# Sheet2.net
KiCad netlist of a schematic drawn in Altium Designer
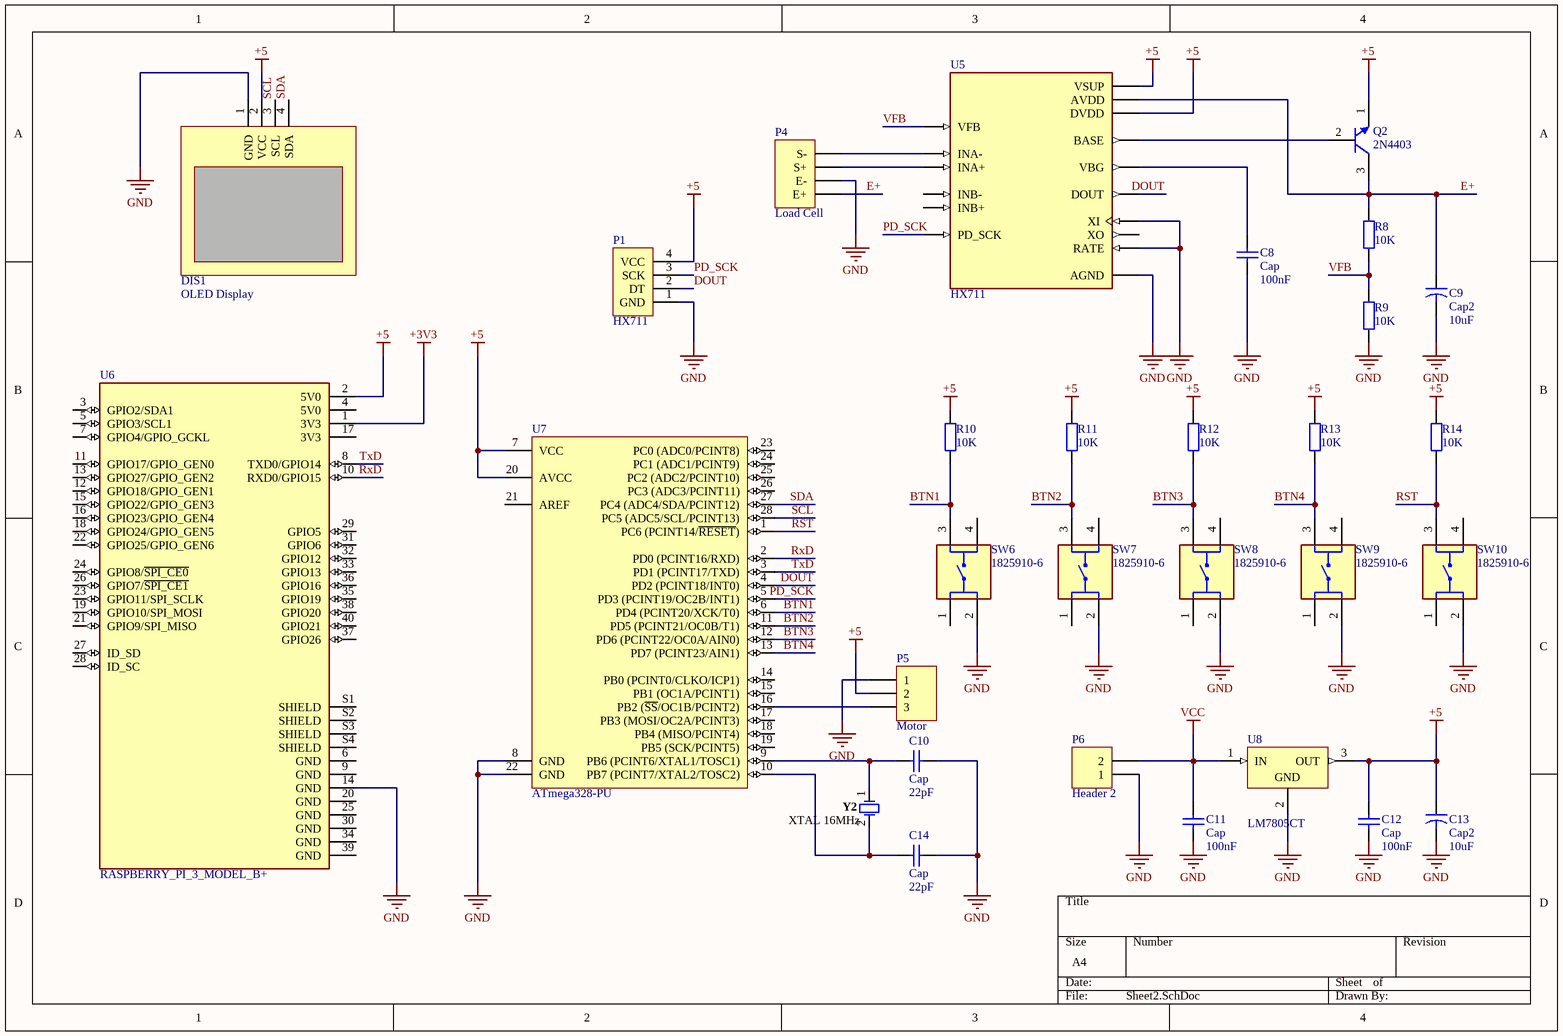
[diagram p0: Sheet2.SchDoc]

(export (version "E")
  (design (tool "Eeschema 10.0.6"))
  (components
    (comp (ref "C8")
      (value "Cap")
      (footprint "RAD-0.2")
      (description "Capacitor")
      (fields (field (name "ALTIUM_VALUE") "100nF") (field (name "PUBLISHER") "Altium Limited"))
      (libsource (lib "Miscellaneous Devices") (part "Cap"))
    )
    (comp (ref "C9")
      (value "Cap2")
      (footprint "R38")
      (description "Capacitor")
      (fields (field (name "ALTIUM_VALUE") "10uF") (field (name "PUBLISHER") "Altium Limited"))
      (libsource (lib "Miscellaneous Devices") (part "Cap2"))
    )
    (comp (ref "C10")
      (value "Cap")
      (footprint "RAD-0.1")
      (description "Capacitor")
      (fields (field (name "ALTIUM_VALUE") "22pF") (field (name "PUBLISHER") "Altium Limited"))
      (libsource (lib "Miscellaneous Devices") (part "Cap"))
    )
    (comp (ref "C11")
      (value "Cap")
      (footprint "RAD-0.2")
      (description "Capacitor")
      (fields (field (name "ALTIUM_VALUE") "100nF") (field (name "PUBLISHER") "Altium Limited"))
      (libsource (lib "Miscellaneous Devices") (part "Cap"))
    )
    (comp (ref "C12")
      (value "Cap")
      (footprint "RAD-0.2")
      (description "Capacitor")
      (fields (field (name "ALTIUM_VALUE") "100nF") (field (name "PUBLISHER") "Altium Limited"))
      (libsource (lib "Miscellaneous Devices") (part "Cap"))
    )
    (comp (ref "C13")
      (value "Cap2")
      (footprint "R38")
      (description "Capacitor")
      (fields (field (name "ALTIUM_VALUE") "10uF") (field (name "PUBLISHER") "Altium Limited"))
      (libsource (lib "Miscellaneous Devices") (part "Cap2"))
    )
    (comp (ref "C14")
      (value "Cap")
      (footprint "RAD-0.1")
      (description "Capacitor")
      (fields (field (name "ALTIUM_VALUE") "22pF") (field (name "PUBLISHER") "Altium Limited"))
      (libsource (lib "Miscellaneous Devices") (part "Cap"))
    )
    (comp (ref "DIS1")
      (value "OLED Display")
      (footprint "OLED12864I2C")
      (libsource (lib "OLED12864I2C") (part "OLED12864I2C"))
    )
    (comp (ref "P1")
      (value "HX711")
      (footprint "HDR1X4")
      (description "Header, 4-Pin")
      (fields (field (name "PUBLISHER") "Altium Limited"))
      (libsource (lib "") (part "Header 4_1"))
    )
    (comp (ref "P4")
      (value "Load Cell")
      (footprint "HDR1X4")
      (description "Load Cell Connector, 4-Pin")
      (fields (field (name "PUBLISHER") "Altium Limited"))
      (libsource (lib "Miscellaneous Connectors") (part "Header 4"))
    )
    (comp (ref "P5")
      (value "Motor")
      (footprint "HDR1X3")
      (description "Header, 3-Pin")
      (fields (field (name "PUBLISHER") "Altium Limited"))
      (libsource (lib "Miscellaneous Connectors") (part "Header 3"))
    )
    (comp (ref "P6")
      (value "Header 2")
      (footprint "HDR1X2")
      (description "Header, 2-Pin")
      (fields (field (name "PUBLISHER") "Altium Limited"))
      (libsource (lib "Miscellaneous Connectors") (part "Header 2"))
    )
    (comp (ref "Q2")
      (value "2N4403")
      (footprint "ONSC-TO-92-3-29-11_AM_BL")
      (description "General Purpose Transistor, NPN Silicon, 3-Pin TO-92, Pb-Free, Ammo Box")
      (fields (field (name "PARTNUMBER") "2N4401RLRPG") (field (name "MANUFACTURER") "On Semiconductor"))
      (libsource (lib "Altium Content Vault") (part "ONSC-NPN-E1B2C3-3"))
    )
    (comp (ref "R8")
      (value "10K")
      (footprint "AXIAL-0.4")
      (description "Resistor")
      (fields (field (name "PUBLISHER") "Altium Limited"))
      (libsource (lib "Miscellaneous Devices") (part "Res2"))
    )
    (comp (ref "R9")
      (value "10K")
      (footprint "AXIAL-0.4")
      (description "Resistor")
      (fields (field (name "PUBLISHER") "Altium Limited"))
      (libsource (lib "Miscellaneous Devices") (part "Res2"))
    )
    (comp (ref "R10")
      (value "10K")
      (footprint "AXIAL-0.4")
      (description "Resistor")
      (fields (field (name "PUBLISHER") "Altium Limited"))
      (libsource (lib "Miscellaneous Devices") (part "Res2"))
    )
    (comp (ref "R11")
      (value "10K")
      (footprint "AXIAL-0.4")
      (description "Resistor")
      (fields (field (name "PUBLISHER") "Altium Limited"))
      (libsource (lib "Miscellaneous Devices") (part "Res2"))
    )
    (comp (ref "R12")
      (value "10K")
      (footprint "AXIAL-0.4")
      (description "Resistor")
      (fields (field (name "PUBLISHER") "Altium Limited"))
      (libsource (lib "Miscellaneous Devices") (part "Res2"))
    )
    (comp (ref "R13")
      (value "10K")
      (footprint "AXIAL-0.4")
      (description "Resistor")
      (fields (field (name "PUBLISHER") "Altium Limited"))
      (libsource (lib "Miscellaneous Devices") (part "Res2"))
    )
    (comp (ref "R14")
      (value "10K")
      (footprint "AXIAL-0.4")
      (description "Resistor")
      (fields (field (name "PUBLISHER") "Altium Limited"))
      (libsource (lib "Miscellaneous Devices") (part "Res2"))
    )
    (comp (ref "SW6")
      (value "1825910-6")
      (footprint "SW_1825910-6-4")
      (description "Switch Tactile OFF (ON) SPST Round Button PC Pins 0.05A 24VDC 100000Cycles 1.57N Thru-Hole Loose")
      (libsource (lib "1825910-6") (part "1825910-6"))
    )
    (comp (ref "SW7")
      (value "1825910-6")
      (footprint "SW_1825910-6-4")
      (description "Switch Tactile OFF (ON) SPST Round Button PC Pins 0.05A 24VDC 100000Cycles 1.57N Thru-Hole Loose")
      (libsource (lib "1825910-6") (part "1825910-6"))
    )
    (comp (ref "SW8")
      (value "1825910-6")
      (footprint "SW_1825910-6-4")
      (description "Switch Tactile OFF (ON) SPST Round Button PC Pins 0.05A 24VDC 100000Cycles 1.57N Thru-Hole Loose")
      (libsource (lib "1825910-6") (part "1825910-6"))
    )
    (comp (ref "SW9")
      (value "1825910-6")
      (footprint "SW_1825910-6-4")
      (description "Switch Tactile OFF (ON) SPST Round Button PC Pins 0.05A 24VDC 100000Cycles 1.57N Thru-Hole Loose")
      (libsource (lib "1825910-6") (part "1825910-6"))
    )
    (comp (ref "SW10")
      (value "1825910-6")
      (footprint "SW_1825910-6-4")
      (description "Switch Tactile OFF (ON) SPST Round Button PC Pins 0.05A 24VDC 100000Cycles 1.57N Thru-Hole Loose")
      (libsource (lib "1825910-6") (part "1825910-6"))
    )
    (comp (ref "U5")
      (value "HX711")
      (footprint "SOP127P600X180-16N")
      (libsource (lib "HX711") (part "HX711"))
    )
    (comp (ref "U6")
      (value "RASPBERRY_PI_3_MODEL_B+")
      (footprint "MODULE_RASPBERRY_PI_3_MODEL_B+")
      (description "BCM2835 Raspberry Pi Model B+ - ARM11, VideoCore MPU Embedded Evaluation Board")
      (libsource (lib "RASPBERRY_PI_3_MODEL_B_") (part "RASPBERRY_PI_3_MODEL_B+"))
    )
    (comp (ref "U7")
      (value "ATmega328-PU")
      (footprint "28P3")
      (libsource (lib "Altium Content Vault") (part "MC-8B-ATM48-IL28"))
    )
    (comp (ref "U8")
      (value "LM7805CT")
      (footprint "FAIR-TO-220-3")
      (description "Positive Voltage Regulator, 5 V, 1 A, -40 to 125 degC, 3-Pin TO-220, RoHS, Tube")
      (fields (field (name "MANUFACTURER") "FairchildSemiconductor"))
      (libsource (lib "Altium Content Vault") (part "FAIR-LM7805CT-TO220-3"))
    )
    (comp (ref "Y2")
      (value "XTAL 16MHz")
      (footprint "FOX-FOXSLF-2_V")
      (description "Resistance Weld Thru-Hole Crystal, 12 MHz, +/-30 ppm, -20 to 70 degC, 2-Pin THD, RoHS, Bulk")
      (libsource (lib "Altium Content Vault") (part "XTAL-1-2-2"))
    )
  )
  (nets
    (net (code "1") (name "+3V3") (class "Default")
      (node (ref "U6") (pin "1") (pinfunction "3V3_1") (pintype "power_in"))
    )
    (net (code "2") (name "+5") (class "Default")
      (node (ref "C12") (pin "2") (pinfunction "2_2") (pintype "passive"))
      (node (ref "C13") (pin "1") (pinfunction "1_1") (pintype "passive"))
      (node (ref "DIS1") (pin "2") (pinfunction "VCC_2") (pintype "passive"))
      (node (ref "P1") (pin "4") (pinfunction "VCC_4") (pintype "passive"))
      (node (ref "P5") (pin "2") (pinfunction "2_2") (pintype "passive"))
      (node (ref "Q2") (pin "1") (pinfunction "E_1") (pintype "passive"))
      (node (ref "R10") (pin "2") (pinfunction "2_2") (pintype "passive"))
      (node (ref "R11") (pin "2") (pinfunction "2_2") (pintype "passive"))
      (node (ref "R12") (pin "2") (pinfunction "2_2") (pintype "passive"))
      (node (ref "R13") (pin "2") (pinfunction "2_2") (pintype "passive"))
      (node (ref "R14") (pin "2") (pinfunction "2_2") (pintype "passive"))
      (node (ref "U5") (pin "1") (pinfunction "VSUP_1") (pintype "power_in"))
      (node (ref "U5") (pin "16") (pinfunction "DVDD_16") (pintype "power_in"))
      (node (ref "U6") (pin "2") (pinfunction "5V0_2") (pintype "power_in"))
      (node (ref "U7") (pin "20") (pinfunction "AVCC_20") (pintype "power_in"))
      (node (ref "U7") (pin "7") (pinfunction "VCC_7") (pintype "power_in"))
      (node (ref "U8") (pin "3") (pinfunction "OUT_3") (pintype "output"))
    )
    (net (code "3") (name "/BTN1") (class "Default")
      (node (ref "R10") (pin "1") (pinfunction "1_1") (pintype "passive"))
      (node (ref "SW6") (pin "3") (pinfunction "3_3") (pintype "passive"))
      (node (ref "U7") (pin "6") (pinfunction "PD4_(PCINT20/XCK/T0)_6") (pintype "bidirectional"))
    )
    (net (code "4") (name "/BTN2") (class "Default")
      (node (ref "R11") (pin "1") (pinfunction "1_1") (pintype "passive"))
      (node (ref "SW7") (pin "3") (pinfunction "3_3") (pintype "passive"))
      (node (ref "U7") (pin "11") (pinfunction "PD5_(PCINT21/OC0B/T1)_11") (pintype "bidirectional"))
    )
    (net (code "5") (name "/BTN3") (class "Default")
      (node (ref "R12") (pin "1") (pinfunction "1_1") (pintype "passive"))
      (node (ref "SW8") (pin "3") (pinfunction "3_3") (pintype "passive"))
      (node (ref "U7") (pin "12") (pinfunction "PD6_(PCINT22/OC0A/AIN0)_12") (pintype "bidirectional"))
    )
    (net (code "6") (name "/BTN4") (class "Default")
      (node (ref "R13") (pin "1") (pinfunction "1_1") (pintype "passive"))
      (node (ref "SW9") (pin "3") (pinfunction "3_3") (pintype "passive"))
      (node (ref "U7") (pin "13") (pinfunction "PD7_(PCINT23/AIN1)_13") (pintype "bidirectional"))
    )
    (net (code "7") (name "/DOUT") (class "Default")
      (node (ref "P1") (pin "2") (pinfunction "DT_2") (pintype "passive"))
      (node (ref "U5") (pin "12") (pinfunction "DOUT_12") (pintype "output"))
      (node (ref "U7") (pin "4") (pinfunction "PD2_(PCINT18/INT0)_4") (pintype "bidirectional"))
    )
    (net (code "8") (name "/E+") (class "Default")
      (node (ref "C9") (pin "1") (pinfunction "1_1") (pintype "passive"))
      (node (ref "P4") (pin "1") (pinfunction "E+_1") (pintype "passive"))
      (node (ref "Q2") (pin "3") (pinfunction "C_3") (pintype "passive"))
      (node (ref "R8") (pin "2") (pinfunction "2_2") (pintype "passive"))
      (node (ref "U5") (pin "3") (pinfunction "AVDD_3") (pintype "power_in"))
    )
    (net (code "9") (name "/PD_SCK") (class "Default")
      (node (ref "P1") (pin "3") (pinfunction "SCK_3") (pintype "passive"))
      (node (ref "U5") (pin "11") (pinfunction "PD_SCK_11") (pintype "input"))
      (node (ref "U7") (pin "5") (pinfunction "PD3_(PCINT19/OC2B/INT1)_5") (pintype "bidirectional"))
    )
    (net (code "10") (name "/RST") (class "Default")
      (node (ref "R14") (pin "1") (pinfunction "1_1") (pintype "passive"))
      (node (ref "SW10") (pin "3") (pinfunction "3_3") (pintype "passive"))
      (node (ref "U7") (pin "1") (pinfunction "PC6_(PCINT14/~{RESET})_1") (pintype "bidirectional"))
    )
    (net (code "11") (name "/RxD") (class "Default")
      (node (ref "U6") (pin "10") (pinfunction "RXD0/GPIO15_10") (pintype "bidirectional"))
      (node (ref "U7") (pin "2") (pinfunction "PD0_(PCINT16/RXD)_2") (pintype "bidirectional"))
    )
    (net (code "12") (name "/SCL") (class "Default")
      (node (ref "DIS1") (pin "3") (pinfunction "SCL_3") (pintype "passive"))
      (node (ref "U7") (pin "28") (pinfunction "PC5_(ADC5/SCL/PCINT13)_28") (pintype "bidirectional"))
    )
    (net (code "13") (name "/SDA") (class "Default")
      (node (ref "DIS1") (pin "4") (pinfunction "SDA_4") (pintype "passive"))
      (node (ref "U7") (pin "27") (pinfunction "PC4_(ADC4/SDA/PCINT12)_27") (pintype "bidirectional"))
    )
    (net (code "14") (name "/TxD") (class "Default")
      (node (ref "U6") (pin "8") (pinfunction "TXD0/GPIO14_8") (pintype "bidirectional"))
      (node (ref "U7") (pin "3") (pinfunction "PD1_(PCINT17/TXD)_3") (pintype "bidirectional"))
    )
    (net (code "15") (name "/VFB") (class "Default")
      (node (ref "R8") (pin "1") (pinfunction "1_1") (pintype "passive"))
      (node (ref "R9") (pin "2") (pinfunction "2_2") (pintype "passive"))
      (node (ref "U5") (pin "4") (pinfunction "VFB_4") (pintype "input"))
    )
    (net (code "16") (name "GND") (class "Default")
      (node (ref "C10") (pin "2") (pinfunction "2_2") (pintype "passive"))
      (node (ref "C11") (pin "1") (pinfunction "1_1") (pintype "passive"))
      (node (ref "C12") (pin "1") (pinfunction "1_1") (pintype "passive"))
      (node (ref "C13") (pin "2") (pinfunction "2_2") (pintype "passive"))
      (node (ref "C14") (pin "2") (pinfunction "2_2") (pintype "passive"))
      (node (ref "C8") (pin "1") (pinfunction "1_1") (pintype "passive"))
      (node (ref "C9") (pin "2") (pinfunction "2_2") (pintype "passive"))
      (node (ref "DIS1") (pin "1") (pinfunction "GND_1") (pintype "passive"))
      (node (ref "P1") (pin "1") (pinfunction "GND_1") (pintype "passive"))
      (node (ref "P4") (pin "2") (pinfunction "E-_2") (pintype "passive"))
      (node (ref "P5") (pin "1") (pinfunction "1_1") (pintype "passive"))
      (node (ref "P6") (pin "1") (pinfunction "1_1") (pintype "passive"))
      (node (ref "R9") (pin "1") (pinfunction "1_1") (pintype "passive"))
      (node (ref "SW10") (pin "2") (pinfunction "2_2") (pintype "passive"))
      (node (ref "SW6") (pin "2") (pinfunction "2_2") (pintype "passive"))
      (node (ref "SW7") (pin "2") (pinfunction "2_2") (pintype "passive"))
      (node (ref "SW8") (pin "2") (pinfunction "2_2") (pintype "passive"))
      (node (ref "SW9") (pin "2") (pinfunction "2_2") (pintype "passive"))
      (node (ref "U5") (pin "14") (pinfunction "XI_14") (pintype "input"))
      (node (ref "U5") (pin "15") (pinfunction "RATE_15") (pintype "input"))
      (node (ref "U5") (pin "5") (pinfunction "AGND_5") (pintype "power_in"))
      (node (ref "U6") (pin "14") (pinfunction "GND_14") (pintype "power_in"))
      (node (ref "U7") (pin "22") (pinfunction "GND_22") (pintype "power_in"))
      (node (ref "U7") (pin "8") (pinfunction "GND_8") (pintype "power_in"))
      (node (ref "U8") (pin "2") (pinfunction "GND_2") (pintype "power_in"))
    )
    (net (code "17") (name "Net-(P4-S+)") (class "Default")
      (node (ref "P4") (pin "3") (pinfunction "S+_3") (pintype "passive"))
      (node (ref "U5") (pin "8") (pinfunction "INA+_8") (pintype "input"))
    )
    (net (code "18") (name "Net-(P4-S-)") (class "Default")
      (node (ref "P4") (pin "4") (pinfunction "S-_4") (pintype "passive"))
      (node (ref "U5") (pin "7") (pinfunction "INA-_7") (pintype "input"))
    )
    (net (code "19") (name "Net-(Q2-B)") (class "Default")
      (node (ref "Q2") (pin "2") (pinfunction "B_2") (pintype "passive"))
      (node (ref "U5") (pin "2") (pinfunction "BASE_2") (pintype "output"))
    )
    (net (code "20") (name "Net-(U5-VBG)") (class "Default")
      (node (ref "C8") (pin "2") (pinfunction "2_2") (pintype "passive"))
      (node (ref "U5") (pin "6") (pinfunction "VBG_6") (pintype "output"))
    )
    (net (code "21") (name "Net-(U7-PB2_(~{SS}{slash}OC1B{slash}PCINT2))") (class "Default")
      (node (ref "P5") (pin "3") (pinfunction "3_3") (pintype "passive"))
      (node (ref "U7") (pin "16") (pinfunction "PB2_(~{SS}/OC1B/PCINT2)_16") (pintype "bidirectional"))
    )
    (net (code "22") (name "Net-(U7-PB6_(PCINT6{slash}XTAL1{slash}TOSC1))") (class "Default")
      (node (ref "C10") (pin "1") (pinfunction "1_1") (pintype "passive"))
      (node (ref "U7") (pin "9") (pinfunction "PB6_(PCINT6/XTAL1/TOSC1)_9") (pintype "bidirectional"))
      (node (ref "Y2") (pin "1") (pinfunction "1_1") (pintype "passive"))
    )
    (net (code "23") (name "Net-(U7-PB7_(PCINT7{slash}XTAL2{slash}TOSC2))") (class "Default")
      (node (ref "C14") (pin "1") (pinfunction "1_1") (pintype "passive"))
      (node (ref "U7") (pin "10") (pinfunction "PB7_(PCINT7/XTAL2/TOSC2)_10") (pintype "bidirectional"))
      (node (ref "Y2") (pin "2") (pinfunction "2_2") (pintype "passive"))
    )
    (net (code "24") (name "VCC") (class "Default")
      (node (ref "C11") (pin "2") (pinfunction "2_2") (pintype "passive"))
      (node (ref "P6") (pin "2") (pinfunction "2_2") (pintype "passive"))
      (node (ref "U8") (pin "1") (pinfunction "IN_1") (pintype "input"))
    )
    (net (code "25") (name "unconnected-(SW6-Pad1)") (class "Default")
      (node (ref "SW6") (pin "1") (pinfunction "1_1") (pintype "passive"))
    )
    (net (code "26") (name "unconnected-(SW6-Pad4)") (class "Default")
      (node (ref "SW6") (pin "4") (pinfunction "4_4") (pintype "passive"))
    )
    (net (code "27") (name "unconnected-(SW7-Pad1)") (class "Default")
      (node (ref "SW7") (pin "1") (pinfunction "1_1") (pintype "passive"))
    )
    (net (code "28") (name "unconnected-(SW7-Pad4)") (class "Default")
      (node (ref "SW7") (pin "4") (pinfunction "4_4") (pintype "passive"))
    )
    (net (code "29") (name "unconnected-(SW8-Pad1)") (class "Default")
      (node (ref "SW8") (pin "1") (pinfunction "1_1") (pintype "passive"))
    )
    (net (code "30") (name "unconnected-(SW8-Pad4)") (class "Default")
      (node (ref "SW8") (pin "4") (pinfunction "4_4") (pintype "passive"))
    )
    (net (code "31") (name "unconnected-(SW9-Pad1)") (class "Default")
      (node (ref "SW9") (pin "1") (pinfunction "1_1") (pintype "passive"))
    )
    (net (code "32") (name "unconnected-(SW9-Pad4)") (class "Default")
      (node (ref "SW9") (pin "4") (pinfunction "4_4") (pintype "passive"))
    )
    (net (code "33") (name "unconnected-(SW10-Pad1)") (class "Default")
      (node (ref "SW10") (pin "1") (pinfunction "1_1") (pintype "passive"))
    )
    (net (code "34") (name "unconnected-(SW10-Pad4)") (class "Default")
      (node (ref "SW10") (pin "4") (pinfunction "4_4") (pintype "passive"))
    )
    (net (code "35") (name "unconnected-(U5-INB+-Pad10)") (class "Default")
      (node (ref "U5") (pin "10") (pinfunction "INB+_10") (pintype "input"))
    )
    (net (code "36") (name "unconnected-(U5-INB--Pad9)") (class "Default")
      (node (ref "U5") (pin "9") (pinfunction "INB-_9") (pintype "input"))
    )
    (net (code "37") (name "unconnected-(U5-XO-Pad13)") (class "Default")
      (node (ref "U5") (pin "13") (pinfunction "XO_13") (pintype "output"))
    )
    (net (code "38") (name "unconnected-(U6-3V3-Pad17)") (class "Default")
      (node (ref "U6") (pin "17") (pinfunction "3V3_17") (pintype "power_in"))
    )
    (net (code "39") (name "unconnected-(U6-5V0-Pad4)") (class "Default")
      (node (ref "U6") (pin "4") (pinfunction "5V0_4") (pintype "power_in"))
    )
    (net (code "40") (name "unconnected-(U6-GND-Pad6)") (class "Default")
      (node (ref "U6") (pin "6") (pinfunction "GND_6") (pintype "power_in"))
    )
    (net (code "41") (name "unconnected-(U6-GND-Pad9)") (class "Default")
      (node (ref "U6") (pin "9") (pinfunction "GND_9") (pintype "power_in"))
    )
    (net (code "42") (name "unconnected-(U6-GND-Pad20)") (class "Default")
      (node (ref "U6") (pin "20") (pinfunction "GND_20") (pintype "power_in"))
    )
    (net (code "43") (name "unconnected-(U6-GND-Pad25)") (class "Default")
      (node (ref "U6") (pin "25") (pinfunction "GND_25") (pintype "power_in"))
    )
    (net (code "44") (name "unconnected-(U6-GND-Pad30)") (class "Default")
      (node (ref "U6") (pin "30") (pinfunction "GND_30") (pintype "power_in"))
    )
    (net (code "45") (name "unconnected-(U6-GND-Pad34)") (class "Default")
      (node (ref "U6") (pin "34") (pinfunction "GND_34") (pintype "power_in"))
    )
    (net (code "46") (name "unconnected-(U6-GND-Pad39)") (class "Default")
      (node (ref "U6") (pin "39") (pinfunction "GND_39") (pintype "power_in"))
    )
    (net (code "47") (name "unconnected-(U6-GPIO2{slash}SDA1-Pad3)") (class "Default")
      (node (ref "U6") (pin "3") (pinfunction "GPIO2/SDA1_3") (pintype "bidirectional"))
    )
    (net (code "48") (name "unconnected-(U6-GPIO3{slash}SCL1-Pad5)") (class "Default")
      (node (ref "U6") (pin "5") (pinfunction "GPIO3/SCL1_5") (pintype "bidirectional"))
    )
    (net (code "49") (name "unconnected-(U6-GPIO4{slash}GPIO_GCKL-Pad7)") (class "Default")
      (node (ref "U6") (pin "7") (pinfunction "GPIO4/GPIO_GCKL_7") (pintype "bidirectional"))
    )
    (net (code "50") (name "unconnected-(U6-GPIO5-Pad29)") (class "Default")
      (node (ref "U6") (pin "29") (pinfunction "GPIO5_29") (pintype "bidirectional"))
    )
    (net (code "51") (name "unconnected-(U6-GPIO6-Pad31)") (class "Default")
      (node (ref "U6") (pin "31") (pinfunction "GPIO6_31") (pintype "bidirectional"))
    )
    (net (code "52") (name "unconnected-(U6-GPIO7{slash}~{SPI_CE1}-Pad26)") (class "Default")
      (node (ref "U6") (pin "26") (pinfunction "GPIO7/~{SPI_CE1}_26") (pintype "bidirectional"))
    )
    (net (code "53") (name "unconnected-(U6-GPIO8{slash}~{SPI_CE0}-Pad24)") (class "Default")
      (node (ref "U6") (pin "24") (pinfunction "GPIO8/~{SPI_CE0}_24") (pintype "bidirectional"))
    )
    (net (code "54") (name "unconnected-(U6-GPIO9{slash}SPI_MISO-Pad21)") (class "Default")
      (node (ref "U6") (pin "21") (pinfunction "GPIO9/SPI_MISO_21") (pintype "bidirectional"))
    )
    (net (code "55") (name "unconnected-(U6-GPIO10{slash}SPI_MOSI-Pad19)") (class "Default")
      (node (ref "U6") (pin "19") (pinfunction "GPIO10/SPI_MOSI_19") (pintype "bidirectional"))
    )
    (net (code "56") (name "unconnected-(U6-GPIO11{slash}SPI_SCLK-Pad23)") (class "Default")
      (node (ref "U6") (pin "23") (pinfunction "GPIO11/SPI_SCLK_23") (pintype "bidirectional"))
    )
    (net (code "57") (name "unconnected-(U6-GPIO12-Pad32)") (class "Default")
      (node (ref "U6") (pin "32") (pinfunction "GPIO12_32") (pintype "bidirectional"))
    )
    (net (code "58") (name "unconnected-(U6-GPIO13-Pad33)") (class "Default")
      (node (ref "U6") (pin "33") (pinfunction "GPIO13_33") (pintype "bidirectional"))
    )
    (net (code "59") (name "unconnected-(U6-GPIO16-Pad36)") (class "Default")
      (node (ref "U6") (pin "36") (pinfunction "GPIO16_36") (pintype "bidirectional"))
    )
    (net (code "60") (name "unconnected-(U6-GPIO17{slash}GPIO_GEN0-Pad11)") (class "Default")
      (node (ref "U6") (pin "11") (pinfunction "GPIO17/GPIO_GEN0_11") (pintype "bidirectional"))
    )
    (net (code "61") (name "unconnected-(U6-GPIO18{slash}GPIO_GEN1-Pad12)") (class "Default")
      (node (ref "U6") (pin "12") (pinfunction "GPIO18/GPIO_GEN1_12") (pintype "bidirectional"))
    )
    (net (code "62") (name "unconnected-(U6-GPIO19-Pad35)") (class "Default")
      (node (ref "U6") (pin "35") (pinfunction "GPIO19_35") (pintype "bidirectional"))
    )
    (net (code "63") (name "unconnected-(U6-GPIO20-Pad38)") (class "Default")
      (node (ref "U6") (pin "38") (pinfunction "GPIO20_38") (pintype "bidirectional"))
    )
    (net (code "64") (name "unconnected-(U6-GPIO21-Pad40)") (class "Default")
      (node (ref "U6") (pin "40") (pinfunction "GPIO21_40") (pintype "bidirectional"))
    )
    (net (code "65") (name "unconnected-(U6-GPIO22{slash}GPIO_GEN3-Pad15)") (class "Default")
      (node (ref "U6") (pin "15") (pinfunction "GPIO22/GPIO_GEN3_15") (pintype "bidirectional"))
    )
    (net (code "66") (name "unconnected-(U6-GPIO23{slash}GPIO_GEN4-Pad16)") (class "Default")
      (node (ref "U6") (pin "16") (pinfunction "GPIO23/GPIO_GEN4_16") (pintype "bidirectional"))
    )
    (net (code "67") (name "unconnected-(U6-GPIO24{slash}GPIO_GEN5-Pad18)") (class "Default")
      (node (ref "U6") (pin "18") (pinfunction "GPIO24/GPIO_GEN5_18") (pintype "bidirectional"))
    )
    (net (code "68") (name "unconnected-(U6-GPIO25{slash}GPIO_GEN6-Pad22)") (class "Default")
      (node (ref "U6") (pin "22") (pinfunction "GPIO25/GPIO_GEN6_22") (pintype "bidirectional"))
    )
    (net (code "69") (name "unconnected-(U6-GPIO26-Pad37)") (class "Default")
      (node (ref "U6") (pin "37") (pinfunction "GPIO26_37") (pintype "bidirectional"))
    )
    (net (code "70") (name "unconnected-(U6-GPIO27{slash}GPIO_GEN2-Pad13)") (class "Default")
      (node (ref "U6") (pin "13") (pinfunction "GPIO27/GPIO_GEN2_13") (pintype "bidirectional"))
    )
    (net (code "71") (name "unconnected-(U6-ID_SC-Pad28)") (class "Default")
      (node (ref "U6") (pin "28") (pinfunction "ID_SC_28") (pintype "bidirectional"))
    )
    (net (code "72") (name "unconnected-(U6-ID_SD-Pad27)") (class "Default")
      (node (ref "U6") (pin "27") (pinfunction "ID_SD_27") (pintype "bidirectional"))
    )
    (net (code "73") (name "unconnected-(U6-SHIELD-PadS1)") (class "Default")
      (node (ref "U6") (pin "S1") (pinfunction "SHIELD_S1") (pintype "power_in"))
    )
    (net (code "74") (name "unconnected-(U6-SHIELD-PadS2)") (class "Default")
      (node (ref "U6") (pin "S2") (pinfunction "SHIELD_S2") (pintype "power_in"))
    )
    (net (code "75") (name "unconnected-(U6-SHIELD-PadS3)") (class "Default")
      (node (ref "U6") (pin "S3") (pinfunction "SHIELD_S3") (pintype "power_in"))
    )
    (net (code "76") (name "unconnected-(U6-SHIELD-PadS4)") (class "Default")
      (node (ref "U6") (pin "S4") (pinfunction "SHIELD_S4") (pintype "power_in"))
    )
    (net (code "77") (name "unconnected-(U7-AREF-Pad21)") (class "Default")
      (node (ref "U7") (pin "21") (pinfunction "AREF_21") (pintype "power_in"))
    )
    (net (code "78") (name "unconnected-(U7-PB0_(PCINT0{slash}CLKO{slash}ICP1)-Pad14)") (class "Default")
      (node (ref "U7") (pin "14") (pinfunction "PB0_(PCINT0/CLKO/ICP1)_14") (pintype "bidirectional"))
    )
    (net (code "79") (name "unconnected-(U7-PB1_(OC1A{slash}PCINT1)-Pad15)") (class "Default")
      (node (ref "U7") (pin "15") (pinfunction "PB1_(OC1A/PCINT1)_15") (pintype "bidirectional"))
    )
    (net (code "80") (name "unconnected-(U7-PB3_(MOSI{slash}OC2A{slash}PCINT3)-Pad17)") (class "Default")
      (node (ref "U7") (pin "17") (pinfunction "PB3_(MOSI/OC2A/PCINT3)_17") (pintype "bidirectional"))
    )
    (net (code "81") (name "unconnected-(U7-PB4_(MISO{slash}PCINT4)-Pad18)") (class "Default")
      (node (ref "U7") (pin "18") (pinfunction "PB4_(MISO/PCINT4)_18") (pintype "bidirectional"))
    )
    (net (code "82") (name "unconnected-(U7-PB5_(SCK{slash}PCINT5)-Pad19)") (class "Default")
      (node (ref "U7") (pin "19") (pinfunction "PB5_(SCK/PCINT5)_19") (pintype "bidirectional"))
    )
    (net (code "83") (name "unconnected-(U7-PC0_(ADC0{slash}PCINT8)-Pad23)") (class "Default")
      (node (ref "U7") (pin "23") (pinfunction "PC0_(ADC0/PCINT8)_23") (pintype "bidirectional"))
    )
    (net (code "84") (name "unconnected-(U7-PC1_(ADC1{slash}PCINT9)-Pad24)") (class "Default")
      (node (ref "U7") (pin "24") (pinfunction "PC1_(ADC1/PCINT9)_24") (pintype "bidirectional"))
    )
    (net (code "85") (name "unconnected-(U7-PC2_(ADC2{slash}PCINT10)-Pad25)") (class "Default")
      (node (ref "U7") (pin "25") (pinfunction "PC2_(ADC2/PCINT10)_25") (pintype "bidirectional"))
    )
    (net (code "86") (name "unconnected-(U7-PC3_(ADC3{slash}PCINT11)-Pad26)") (class "Default")
      (node (ref "U7") (pin "26") (pinfunction "PC3_(ADC3/PCINT11)_26") (pintype "bidirectional"))
    )
  )
)
